# Wifi_Module_Breakout.net
KiCad netlist of a schematic drawn in EAGLE
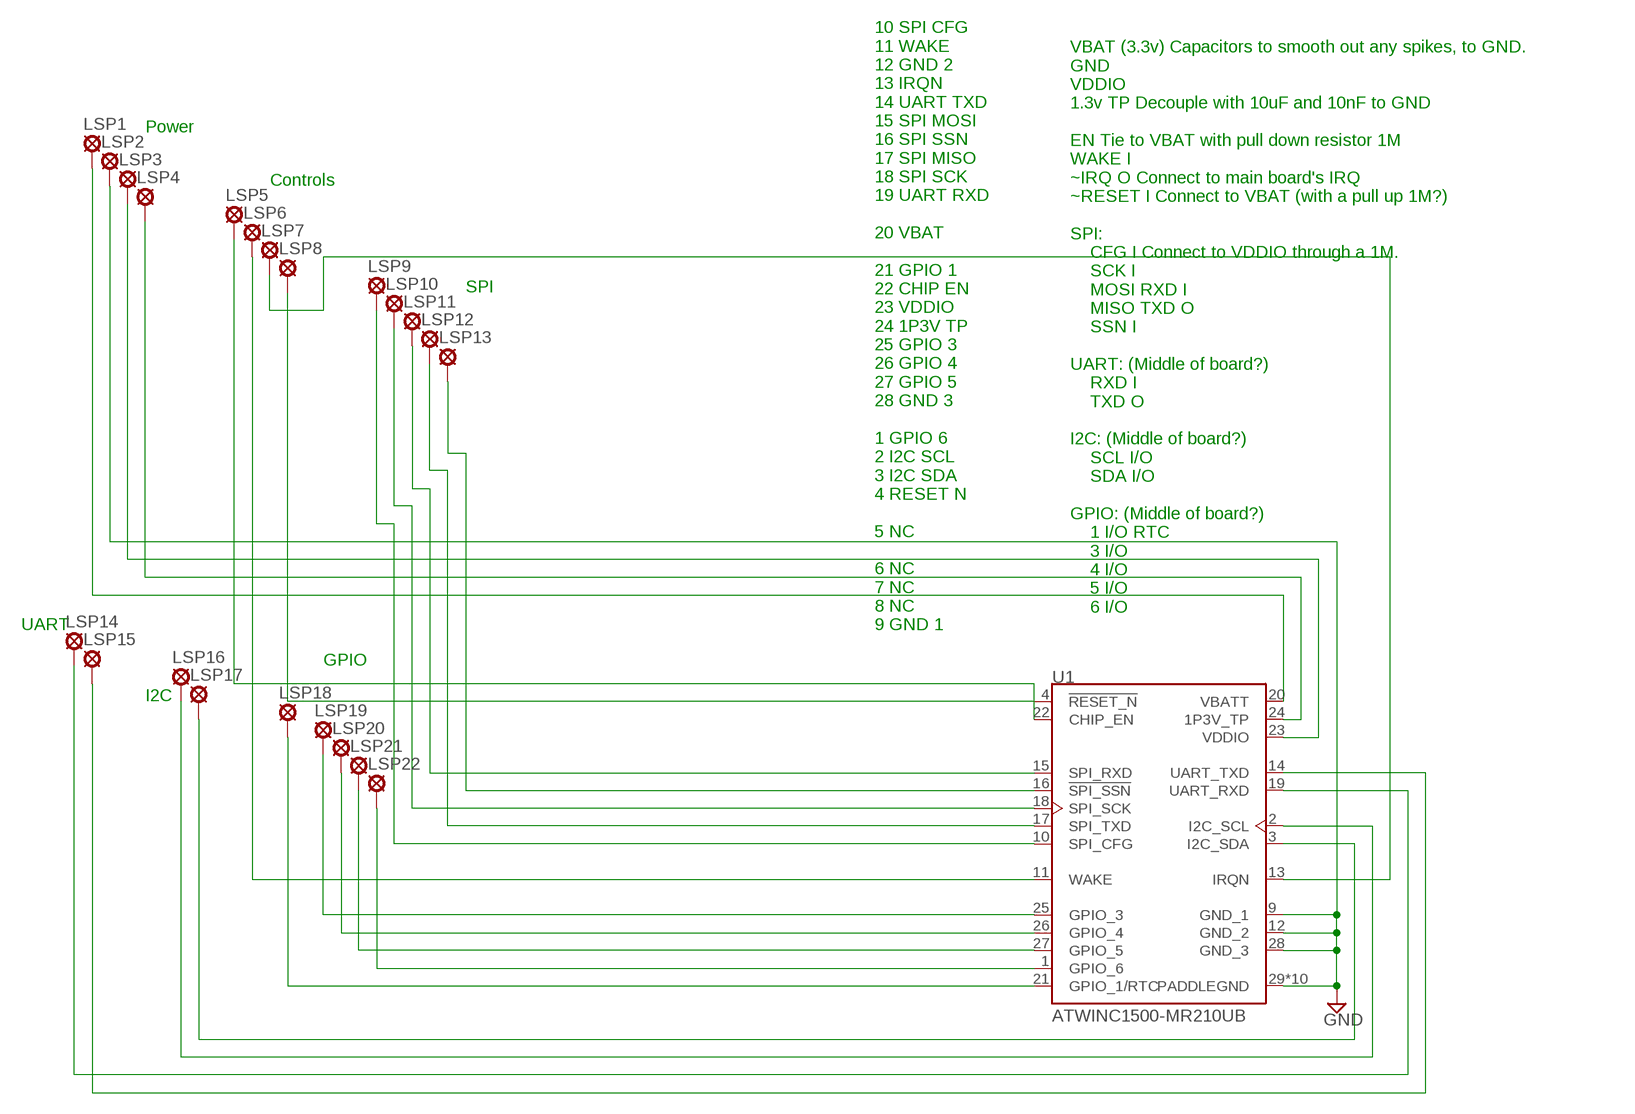
[diagram p0: schematic, sheet 1]

(export (version "E")
  (design (tool "Eeschema 10.0.6"))
  (components
    (comp (ref "LSP1")
      (value "LSP10_CLSP10_C")
      (footprint "eagle-import:LSP10_C")
      (libsource (lib "eagle-import") (part "LSP10_CLSP10_C"))
    )
    (comp (ref "LSP2")
      (value "LSP10_CLSP10_C")
      (footprint "eagle-import:LSP10_C")
      (libsource (lib "eagle-import") (part "LSP10_CLSP10_C"))
    )
    (comp (ref "LSP3")
      (value "LSP10_CLSP10_C")
      (footprint "eagle-import:LSP10_C")
      (libsource (lib "eagle-import") (part "LSP10_CLSP10_C"))
    )
    (comp (ref "LSP4")
      (value "LSP10_CLSP10_C")
      (footprint "eagle-import:LSP10_C")
      (libsource (lib "eagle-import") (part "LSP10_CLSP10_C"))
    )
    (comp (ref "LSP5")
      (value "LSP10_CLSP10_C")
      (footprint "eagle-import:LSP10_C")
      (libsource (lib "eagle-import") (part "LSP10_CLSP10_C"))
    )
    (comp (ref "LSP6")
      (value "LSP10_CLSP10_C")
      (footprint "eagle-import:LSP10_C")
      (libsource (lib "eagle-import") (part "LSP10_CLSP10_C"))
    )
    (comp (ref "LSP7")
      (value "LSP10_CLSP10_C")
      (footprint "eagle-import:LSP10_C")
      (libsource (lib "eagle-import") (part "LSP10_CLSP10_C"))
    )
    (comp (ref "LSP8")
      (value "LSP10_CLSP10_C")
      (footprint "eagle-import:LSP10_C")
      (libsource (lib "eagle-import") (part "LSP10_CLSP10_C"))
    )
    (comp (ref "LSP9")
      (value "LSP10_CLSP10_C")
      (footprint "eagle-import:LSP10_C")
      (libsource (lib "eagle-import") (part "LSP10_CLSP10_C"))
    )
    (comp (ref "LSP10")
      (value "LSP10_CLSP10_C")
      (footprint "eagle-import:LSP10_C")
      (libsource (lib "eagle-import") (part "LSP10_CLSP10_C"))
    )
    (comp (ref "LSP11")
      (value "LSP10_CLSP10_C")
      (footprint "eagle-import:LSP10_C")
      (libsource (lib "eagle-import") (part "LSP10_CLSP10_C"))
    )
    (comp (ref "LSP12")
      (value "LSP10_CLSP10_C")
      (footprint "eagle-import:LSP10_C")
      (libsource (lib "eagle-import") (part "LSP10_CLSP10_C"))
    )
    (comp (ref "LSP13")
      (value "LSP10_CLSP10_C")
      (footprint "eagle-import:LSP10_C")
      (libsource (lib "eagle-import") (part "LSP10_CLSP10_C"))
    )
    (comp (ref "LSP14")
      (value "LSP10_CLSP10_C")
      (footprint "eagle-import:LSP10_C")
      (libsource (lib "eagle-import") (part "LSP10_CLSP10_C"))
    )
    (comp (ref "LSP15")
      (value "LSP10_CLSP10_C")
      (footprint "eagle-import:LSP10_C")
      (libsource (lib "eagle-import") (part "LSP10_CLSP10_C"))
    )
    (comp (ref "LSP16")
      (value "LSP10_CLSP10_C")
      (footprint "eagle-import:LSP10_C")
      (libsource (lib "eagle-import") (part "LSP10_CLSP10_C"))
    )
    (comp (ref "LSP17")
      (value "LSP10_CLSP10_C")
      (footprint "eagle-import:LSP10_C")
      (libsource (lib "eagle-import") (part "LSP10_CLSP10_C"))
    )
    (comp (ref "LSP18")
      (value "LSP10_CLSP10_C")
      (footprint "eagle-import:LSP10_C")
      (libsource (lib "eagle-import") (part "LSP10_CLSP10_C"))
    )
    (comp (ref "LSP19")
      (value "LSP10_CLSP10_C")
      (footprint "eagle-import:LSP10_C")
      (libsource (lib "eagle-import") (part "LSP10_CLSP10_C"))
    )
    (comp (ref "LSP20")
      (value "LSP10_CLSP10_C")
      (footprint "eagle-import:LSP10_C")
      (libsource (lib "eagle-import") (part "LSP10_CLSP10_C"))
    )
    (comp (ref "LSP21")
      (value "LSP10_CLSP10_C")
      (footprint "eagle-import:LSP10_C")
      (libsource (lib "eagle-import") (part "LSP10_CLSP10_C"))
    )
    (comp (ref "LSP22")
      (value "LSP10_CLSP10_C")
      (footprint "eagle-import:LSP10_C")
      (libsource (lib "eagle-import") (part "LSP10_CLSP10_C"))
    )
    (comp (ref "U1")
      (value "ATWINC1500-MR210UB")
      (footprint "eagle-import:MICROCHIP_ATWINC1500-MR210UB")
      (fields (field (name "MF") "Microchip"))
      (libsource (lib "eagle-import") (part "ATWINC1500-MR210UB"))
    )
  )
  (nets
    (net (code "1") (name "GND") (class "Default")
      (node (ref "LSP2") (pin "P$1") (pinfunction "MP_P$1") (pintype "passive"))
      (node (ref "U1") (pin "12") (pinfunction "GND_2_12") (pintype "power_in"))
      (node (ref "U1") (pin "28") (pinfunction "GND_3_28") (pintype "power_in"))
      (node (ref "U1") (pin "29") (pinfunction "PADDLEGND_29") (pintype "power_in"))
      (node (ref "U1") (pin "9") (pinfunction "GND_1_9") (pintype "power_in"))
      (node (ref "U1") (pin "P$1") (pinfunction "PADDLEGND_P$1") (pintype "power_in"))
      (node (ref "U1") (pin "P$2") (pinfunction "PADDLEGND_P$2") (pintype "power_in"))
      (node (ref "U1") (pin "P$3") (pinfunction "PADDLEGND_P$3") (pintype "power_in"))
      (node (ref "U1") (pin "P$4") (pinfunction "PADDLEGND_P$4") (pintype "power_in"))
      (node (ref "U1") (pin "P$5") (pinfunction "PADDLEGND_P$5") (pintype "power_in"))
      (node (ref "U1") (pin "P$6") (pinfunction "PADDLEGND_P$6") (pintype "power_in"))
      (node (ref "U1") (pin "P$7") (pinfunction "PADDLEGND_P$7") (pintype "power_in"))
      (node (ref "U1") (pin "P$8") (pinfunction "PADDLEGND_P$8") (pintype "power_in"))
      (node (ref "U1") (pin "P$9") (pinfunction "PADDLEGND_P$9") (pintype "power_in"))
    )
    (net (code "2") (name "Net-(LSP1-MP)") (class "Default")
      (node (ref "LSP1") (pin "P$1") (pinfunction "MP_P$1") (pintype "passive"))
      (node (ref "U1") (pin "20") (pinfunction "VBATT_20") (pintype "power_in"))
    )
    (net (code "3") (name "Net-(LSP3-MP)") (class "Default")
      (node (ref "LSP3") (pin "P$1") (pinfunction "MP_P$1") (pintype "passive"))
      (node (ref "U1") (pin "23") (pinfunction "VDDIO_23") (pintype "power_in"))
    )
    (net (code "4") (name "Net-(LSP4-MP)") (class "Default")
      (node (ref "LSP4") (pin "P$1") (pinfunction "MP_P$1") (pintype "passive"))
      (node (ref "U1") (pin "24") (pinfunction "1P3V_TP_24") (pintype "power_in"))
    )
    (net (code "5") (name "Net-(LSP5-MP)") (class "Default")
      (node (ref "LSP5") (pin "P$1") (pinfunction "MP_P$1") (pintype "passive"))
      (node (ref "U1") (pin "22") (pinfunction "CHIP_EN_22") (pintype "input"))
    )
    (net (code "6") (name "Net-(LSP6-MP)") (class "Default")
      (node (ref "LSP6") (pin "P$1") (pinfunction "MP_P$1") (pintype "passive"))
      (node (ref "U1") (pin "11") (pinfunction "WAKE_11") (pintype "input"))
    )
    (net (code "7") (name "Net-(LSP7-MP)") (class "Default")
      (node (ref "LSP7") (pin "P$1") (pinfunction "MP_P$1") (pintype "passive"))
      (node (ref "U1") (pin "13") (pinfunction "IRQN_13") (pintype "output"))
    )
    (net (code "8") (name "Net-(LSP8-MP)") (class "Default")
      (node (ref "LSP8") (pin "P$1") (pinfunction "MP_P$1") (pintype "passive"))
      (node (ref "U1") (pin "4") (pinfunction "~{RESET_N}_4") (pintype "input"))
    )
    (net (code "9") (name "Net-(LSP9-MP)") (class "Default")
      (node (ref "LSP9") (pin "P$1") (pinfunction "MP_P$1") (pintype "passive"))
      (node (ref "U1") (pin "10") (pinfunction "SPI_CFG_10") (pintype "input"))
    )
    (net (code "10") (name "Net-(LSP10-MP)") (class "Default")
      (node (ref "LSP10") (pin "P$1") (pinfunction "MP_P$1") (pintype "passive"))
      (node (ref "U1") (pin "18") (pinfunction "SPI_SCK_18") (pintype "input"))
    )
    (net (code "11") (name "Net-(LSP11-MP)") (class "Default")
      (node (ref "LSP11") (pin "P$1") (pinfunction "MP_P$1") (pintype "passive"))
      (node (ref "U1") (pin "15") (pinfunction "SPI_RXD_15") (pintype "input"))
    )
    (net (code "12") (name "Net-(LSP12-MP)") (class "Default")
      (node (ref "LSP12") (pin "P$1") (pinfunction "MP_P$1") (pintype "passive"))
      (node (ref "U1") (pin "17") (pinfunction "SPI_TXD_17") (pintype "output"))
    )
    (net (code "13") (name "Net-(LSP13-MP)") (class "Default")
      (node (ref "LSP13") (pin "P$1") (pinfunction "MP_P$1") (pintype "passive"))
      (node (ref "U1") (pin "16") (pinfunction "~{SPI_SSN}_16") (pintype "input"))
    )
    (net (code "14") (name "Net-(LSP14-MP)") (class "Default")
      (node (ref "LSP14") (pin "P$1") (pinfunction "MP_P$1") (pintype "passive"))
      (node (ref "U1") (pin "19") (pinfunction "UART_RXD_19") (pintype "input"))
    )
    (net (code "15") (name "Net-(LSP15-MP)") (class "Default")
      (node (ref "LSP15") (pin "P$1") (pinfunction "MP_P$1") (pintype "passive"))
      (node (ref "U1") (pin "14") (pinfunction "UART_TXD_14") (pintype "output"))
    )
    (net (code "16") (name "Net-(LSP16-MP)") (class "Default")
      (node (ref "LSP16") (pin "P$1") (pinfunction "MP_P$1") (pintype "passive"))
      (node (ref "U1") (pin "2") (pinfunction "I2C_SCL_2") (pintype "bidirectional"))
    )
    (net (code "17") (name "Net-(LSP17-MP)") (class "Default")
      (node (ref "LSP17") (pin "P$1") (pinfunction "MP_P$1") (pintype "passive"))
      (node (ref "U1") (pin "3") (pinfunction "I2C_SDA_3") (pintype "bidirectional"))
    )
    (net (code "18") (name "Net-(LSP18-MP)") (class "Default")
      (node (ref "LSP18") (pin "P$1") (pinfunction "MP_P$1") (pintype "passive"))
      (node (ref "U1") (pin "21") (pinfunction "GPIO_1/RTC_21") (pintype "input"))
    )
    (net (code "19") (name "Net-(LSP19-MP)") (class "Default")
      (node (ref "LSP19") (pin "P$1") (pinfunction "MP_P$1") (pintype "passive"))
      (node (ref "U1") (pin "25") (pinfunction "GPIO_3_25") (pintype "bidirectional"))
    )
    (net (code "20") (name "Net-(LSP20-MP)") (class "Default")
      (node (ref "LSP20") (pin "P$1") (pinfunction "MP_P$1") (pintype "passive"))
      (node (ref "U1") (pin "26") (pinfunction "GPIO_4_26") (pintype "bidirectional"))
    )
    (net (code "21") (name "Net-(LSP21-MP)") (class "Default")
      (node (ref "LSP21") (pin "P$1") (pinfunction "MP_P$1") (pintype "passive"))
      (node (ref "U1") (pin "27") (pinfunction "GPIO_5_27") (pintype "bidirectional"))
    )
    (net (code "22") (name "Net-(LSP22-MP)") (class "Default")
      (node (ref "LSP22") (pin "P$1") (pinfunction "MP_P$1") (pintype "passive"))
      (node (ref "U1") (pin "1") (pinfunction "GPIO_6_1") (pintype "bidirectional"))
    )
  )
)
